# WordClock_SCH_easyEDA.net
KiCad netlist of a schematic drawn in EasyEDA
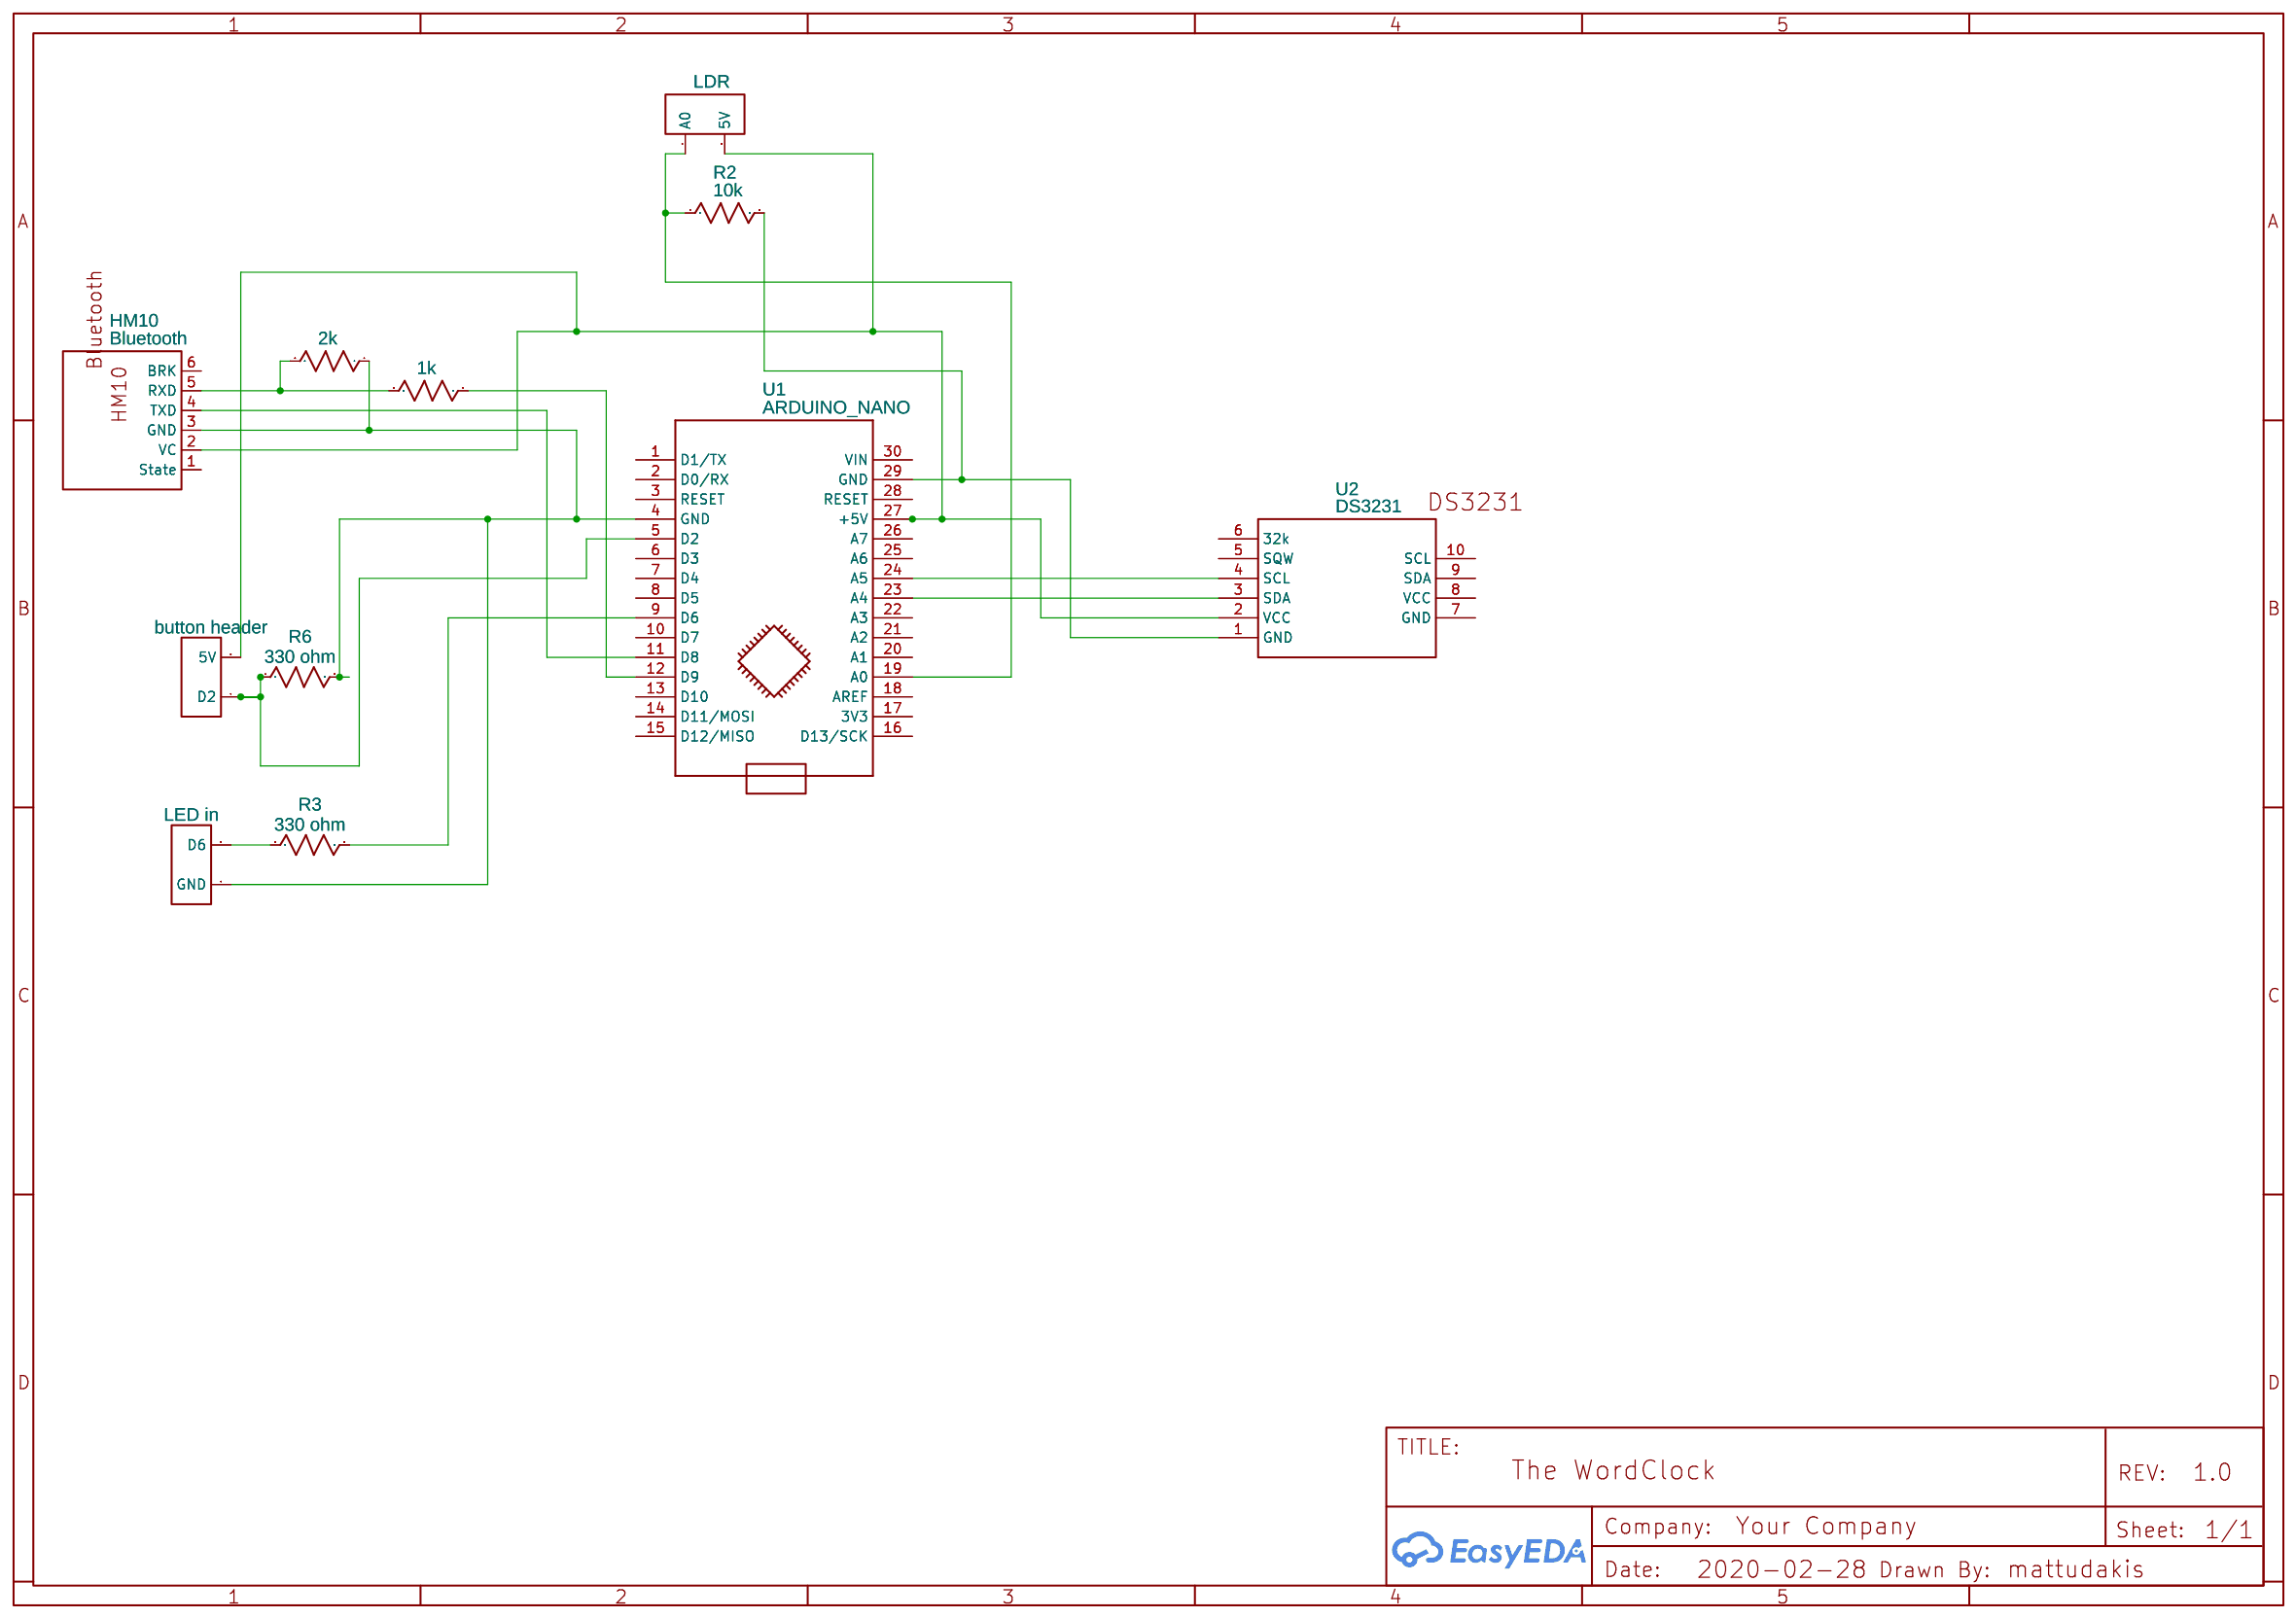
[diagram p0: schematic sheet]

(export (version "E")
  (design (tool "Eeschema 10.0.6"))
  (components
    (comp (ref "H1")
      (value "button header")
      (fields (field (name "BOM_Manufacturer Part") "826629-2") (field (name "BOM_Supplier Part") "C86471"))
      (libsource (lib "") (part "Header-Male-2.54_1x2"))
    )
    (comp (ref "H2")
      (value "LED in")
      (fields (field (name "BOM_Manufacturer Part") "826629-2") (field (name "BOM_Supplier Part") "C86471"))
      (libsource (lib "") (part "Header-Male-2.54_1x2_2"))
    )
    (comp (ref "H3")
      (value "LDR")
      (fields (field (name "BOM_Manufacturer Part") "826629-2") (field (name "BOM_Supplier Part") "C86471"))
      (libsource (lib "") (part "Header-Male-2.54_1x2_1"))
    )
    (comp (ref "HM10") (value "Bluetooth") (libsource (lib "") (part "Bluetooth")))
    (comp (ref "R2") (value "10k") (libsource (lib "") (part "Res_AXIAL-0.5(1/2W)_US")))
    (comp (ref "R3") (value "330 ohm") (libsource (lib "") (part "Res_AXIAL-0.5(1/2W)_US")))
    (comp (ref "R4") (value "2k") (libsource (lib "") (part "Res_AXIAL-0.5(1/2W)_US_1")))
    (comp (ref "R5") (value "1k") (libsource (lib "") (part "Res_AXIAL-0.5(1/2W)_US_1")))
    (comp (ref "R6") (value "330 ohm") (libsource (lib "") (part "Res_AXIAL-0.5(1/2W)_US")))
    (comp (ref "U1") (value "ARDUINO_NANO") (libsource (lib "") (part "ARDUINO_NANO")))
    (comp (ref "U2") (value "DS3231") (libsource (lib "") (part "DS3231")))
  )
  (nets
    (net (code "1") (name "Net-(H1-5V)") (class "Default")
      (node (ref "H1") (pin "2") (pinfunction "5V_2") (pintype "unspecified"))
      (node (ref "H3") (pin "2") (pinfunction "5V_2") (pintype "unspecified"))
      (node (ref "HM10") (pin "2") (pinfunction "VC_2") (pintype "unspecified"))
      (node (ref "U1") (pin "27") (pinfunction "+5V_27") (pintype "unspecified"))
      (node (ref "U2") (pin "2") (pinfunction "VCC_2") (pintype "unspecified"))
    )
    (net (code "2") (name "Net-(H1-D2)") (class "Default")
      (node (ref "H1") (pin "1") (pinfunction "D2_1") (pintype "unspecified"))
      (node (ref "R6") (pin "1") (pinfunction "1_1") (pintype "unspecified"))
      (node (ref "U1") (pin "5") (pinfunction "D2_5") (pintype "unspecified"))
    )
    (net (code "3") (name "Net-(H2-D6)") (class "Default")
      (node (ref "H2") (pin "2") (pinfunction "D6_2") (pintype "unspecified"))
      (node (ref "R3") (pin "1") (pinfunction "1_1") (pintype "unspecified"))
    )
    (net (code "4") (name "Net-(H2-GND)") (class "Default")
      (node (ref "H2") (pin "1") (pinfunction "GND_1") (pintype "unspecified"))
      (node (ref "HM10") (pin "3") (pinfunction "GND_3") (pintype "unspecified"))
      (node (ref "R4") (pin "1") (pinfunction "1_1") (pintype "unspecified"))
      (node (ref "R6") (pin "2") (pinfunction "2_2") (pintype "unspecified"))
      (node (ref "U1") (pin "4") (pinfunction "GND_4") (pintype "unspecified"))
    )
    (net (code "5") (name "Net-(H3-A0)") (class "Default")
      (node (ref "H3") (pin "1") (pinfunction "A0_1") (pintype "unspecified"))
      (node (ref "R2") (pin "1") (pinfunction "1_1") (pintype "unspecified"))
      (node (ref "U1") (pin "19") (pinfunction "A0_19") (pintype "unspecified"))
    )
    (net (code "6") (name "Net-(HM10-RXD)") (class "Default")
      (node (ref "HM10") (pin "5") (pinfunction "RXD_5") (pintype "unspecified"))
      (node (ref "R4") (pin "2") (pinfunction "2_2") (pintype "unspecified"))
      (node (ref "R5") (pin "2") (pinfunction "2_2") (pintype "unspecified"))
    )
    (net (code "7") (name "Net-(HM10-TXD)") (class "Default")
      (node (ref "HM10") (pin "4") (pinfunction "TXD_4") (pintype "unspecified"))
      (node (ref "U1") (pin "11") (pinfunction "D8_11") (pintype "unspecified"))
    )
    (net (code "8") (name "Net-(R2-Pad2)") (class "Default")
      (node (ref "R2") (pin "2") (pinfunction "2_2") (pintype "unspecified"))
      (node (ref "U1") (pin "29") (pinfunction "GND_29") (pintype "unspecified"))
      (node (ref "U2") (pin "1") (pinfunction "GND_1") (pintype "unspecified"))
    )
    (net (code "9") (name "Net-(U1-A4)") (class "Default")
      (node (ref "U1") (pin "23") (pinfunction "A4_23") (pintype "unspecified"))
      (node (ref "U2") (pin "3") (pinfunction "SDA_3") (pintype "unspecified"))
    )
    (net (code "10") (name "Net-(U1-A5)") (class "Default")
      (node (ref "U1") (pin "24") (pinfunction "A5_24") (pintype "unspecified"))
      (node (ref "U2") (pin "4") (pinfunction "SCL_4") (pintype "unspecified"))
    )
    (net (code "11") (name "Net-(U1-D6)") (class "Default")
      (node (ref "R3") (pin "2") (pinfunction "2_2") (pintype "unspecified"))
      (node (ref "U1") (pin "9") (pinfunction "D6_9") (pintype "unspecified"))
    )
    (net (code "12") (name "Net-(U1-D9)") (class "Default")
      (node (ref "R5") (pin "1") (pinfunction "1_1") (pintype "unspecified"))
      (node (ref "U1") (pin "12") (pinfunction "D9_12") (pintype "unspecified"))
    )
    (net (code "13") (name "unconnected-(HM10-BRK-Pad6)") (class "Default")
      (node (ref "HM10") (pin "6") (pinfunction "BRK_6") (pintype "unspecified"))
    )
    (net (code "14") (name "unconnected-(HM10-State-Pad1)") (class "Default")
      (node (ref "HM10") (pin "1") (pinfunction "State_1") (pintype "unspecified"))
    )
    (net (code "15") (name "unconnected-(U1-3V3-Pad17)") (class "Default")
      (node (ref "U1") (pin "17") (pinfunction "3V3_17") (pintype "unspecified"))
    )
    (net (code "16") (name "unconnected-(U1-A1-Pad20)") (class "Default")
      (node (ref "U1") (pin "20") (pinfunction "A1_20") (pintype "unspecified"))
    )
    (net (code "17") (name "unconnected-(U1-A2-Pad21)") (class "Default")
      (node (ref "U1") (pin "21") (pinfunction "A2_21") (pintype "unspecified"))
    )
    (net (code "18") (name "unconnected-(U1-A3-Pad22)") (class "Default")
      (node (ref "U1") (pin "22") (pinfunction "A3_22") (pintype "unspecified"))
    )
    (net (code "19") (name "unconnected-(U1-A6-Pad25)") (class "Default")
      (node (ref "U1") (pin "25") (pinfunction "A6_25") (pintype "unspecified"))
    )
    (net (code "20") (name "unconnected-(U1-A7-Pad26)") (class "Default")
      (node (ref "U1") (pin "26") (pinfunction "A7_26") (pintype "unspecified"))
    )
    (net (code "21") (name "unconnected-(U1-AREF-Pad18)") (class "Default")
      (node (ref "U1") (pin "18") (pinfunction "AREF_18") (pintype "unspecified"))
    )
    (net (code "22") (name "unconnected-(U1-D0{slash}RX-Pad2)") (class "Default")
      (node (ref "U1") (pin "2") (pinfunction "D0/RX_2") (pintype "unspecified"))
    )
    (net (code "23") (name "unconnected-(U1-D1{slash}TX-Pad1)") (class "Default")
      (node (ref "U1") (pin "1") (pinfunction "D1/TX_1") (pintype "unspecified"))
    )
    (net (code "24") (name "unconnected-(U1-D3-Pad6)") (class "Default")
      (node (ref "U1") (pin "6") (pinfunction "D3_6") (pintype "unspecified"))
    )
    (net (code "25") (name "unconnected-(U1-D4-Pad7)") (class "Default")
      (node (ref "U1") (pin "7") (pinfunction "D4_7") (pintype "unspecified"))
    )
    (net (code "26") (name "unconnected-(U1-D5-Pad8)") (class "Default")
      (node (ref "U1") (pin "8") (pinfunction "D5_8") (pintype "unspecified"))
    )
    (net (code "27") (name "unconnected-(U1-D7-Pad10)") (class "Default")
      (node (ref "U1") (pin "10") (pinfunction "D7_10") (pintype "unspecified"))
    )
    (net (code "28") (name "unconnected-(U1-D10-Pad13)") (class "Default")
      (node (ref "U1") (pin "13") (pinfunction "D10_13") (pintype "unspecified"))
    )
    (net (code "29") (name "unconnected-(U1-D11{slash}MOSI-Pad14)") (class "Default")
      (node (ref "U1") (pin "14") (pinfunction "D11/MOSI_14") (pintype "unspecified"))
    )
    (net (code "30") (name "unconnected-(U1-D12{slash}MISO-Pad15)") (class "Default")
      (node (ref "U1") (pin "15") (pinfunction "D12/MISO_15") (pintype "unspecified"))
    )
    (net (code "31") (name "unconnected-(U1-D13{slash}SCK-Pad16)") (class "Default")
      (node (ref "U1") (pin "16") (pinfunction "D13/SCK_16") (pintype "unspecified"))
    )
    (net (code "32") (name "unconnected-(U1-RESET-Pad3)") (class "Default")
      (node (ref "U1") (pin "3") (pinfunction "RESET_3") (pintype "unspecified"))
    )
    (net (code "33") (name "unconnected-(U1-RESET-Pad28)") (class "Default")
      (node (ref "U1") (pin "28") (pinfunction "RESET_28") (pintype "unspecified"))
    )
    (net (code "34") (name "unconnected-(U1-VIN-Pad30)") (class "Default")
      (node (ref "U1") (pin "30") (pinfunction "VIN_30") (pintype "unspecified"))
    )
    (net (code "35") (name "unconnected-(U2-32k-Pad6)") (class "Default")
      (node (ref "U2") (pin "6") (pinfunction "32k_6") (pintype "unspecified"))
    )
    (net (code "36") (name "unconnected-(U2-GND-Pad7)") (class "Default")
      (node (ref "U2") (pin "7") (pinfunction "GND_7") (pintype "unspecified"))
    )
    (net (code "37") (name "unconnected-(U2-SCL-Pad10)") (class "Default")
      (node (ref "U2") (pin "10") (pinfunction "SCL_10") (pintype "unspecified"))
    )
    (net (code "38") (name "unconnected-(U2-SDA-Pad9)") (class "Default")
      (node (ref "U2") (pin "9") (pinfunction "SDA_9") (pintype "unspecified"))
    )
    (net (code "39") (name "unconnected-(U2-SQW-Pad5)") (class "Default")
      (node (ref "U2") (pin "5") (pinfunction "SQW_5") (pintype "unspecified"))
    )
    (net (code "40") (name "unconnected-(U2-VCC-Pad8)") (class "Default")
      (node (ref "U2") (pin "8") (pinfunction "VCC_8") (pintype "unspecified"))
    )
  )
)
